# Driver3.net
KiCad netlist of a schematic drawn in Altium Designer
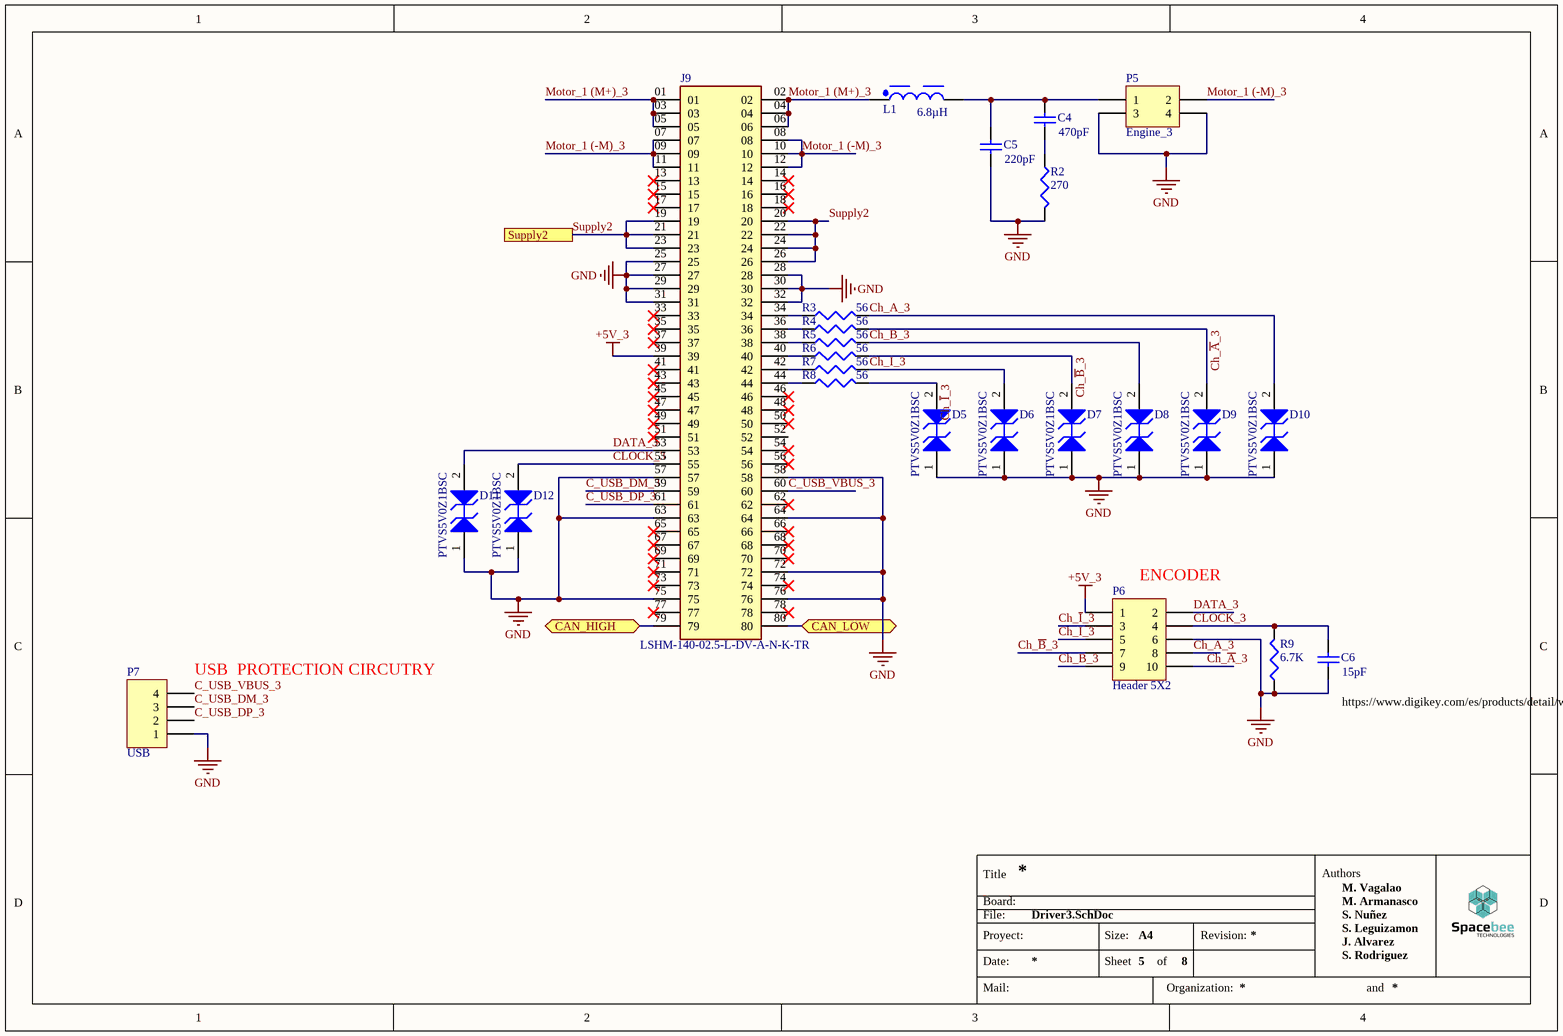
[diagram p0: Driver3.SchDoc]

(export (version "E")
  (design (tool "Eeschema 10.0.6"))
  (components
    (comp (ref "C4")
      (value "470pF")
      (footprint "1608[0603]")
      (description "Capacitor (Semiconductor SIM Model)")
      (fields (field (name "Comment") "Cap Semi") (field (name "PUBLISHER") "Altium Limited"))
      (libsource (lib "Miscellaneous Devices") (part "Cap Semi"))
    )
    (comp (ref "C5")
      (value "220pF")
      (footprint "1608[0603]")
      (description "Capacitor (Semiconductor SIM Model)")
      (fields (field (name "Comment") "Cap Semi") (field (name "PUBLISHER") "Altium Limited"))
      (libsource (lib "Miscellaneous Devices") (part "Cap Semi"))
    )
    (comp (ref "C6")
      (value "15pF")
      (footprint "1608[0603]")
      (description "Capacitor (Semiconductor SIM Model)")
      (fields (field (name "Comment") "Cap Semi") (field (name "PUBLISHER") "Altium Limited"))
      (libsource (lib "Miscellaneous Devices") (part "Cap Semi"))
    )
    (comp (ref "D5")
      (value "PTVS5V0Z1BSC")
      (footprint "SOD993B")
      (fields (field (name "MANUFACTURER") "On Semiconductor") (field (name "PARTNUMBER") "1SMB16CAT3"))
      (libsource (lib "DriverLib") (part "PTVS5V0Z1BSC"))
    )
    (comp (ref "D6")
      (value "PTVS5V0Z1BSC")
      (footprint "SOD993B")
      (fields (field (name "MANUFACTURER") "On Semiconductor") (field (name "PARTNUMBER") "1SMB16CAT3"))
      (libsource (lib "DriverLib") (part "PTVS5V0Z1BSC"))
    )
    (comp (ref "D7")
      (value "PTVS5V0Z1BSC")
      (footprint "SOD993B")
      (fields (field (name "MANUFACTURER") "On Semiconductor") (field (name "PARTNUMBER") "1SMB16CAT3"))
      (libsource (lib "DriverLib") (part "PTVS5V0Z1BSC"))
    )
    (comp (ref "D8")
      (value "PTVS5V0Z1BSC")
      (footprint "SOD993B")
      (fields (field (name "MANUFACTURER") "On Semiconductor") (field (name "PARTNUMBER") "1SMB16CAT3"))
      (libsource (lib "DriverLib") (part "PTVS5V0Z1BSC"))
    )
    (comp (ref "D9")
      (value "PTVS5V0Z1BSC")
      (footprint "SOD993B")
      (fields (field (name "MANUFACTURER") "On Semiconductor") (field (name "PARTNUMBER") "1SMB16CAT3"))
      (libsource (lib "DriverLib") (part "PTVS5V0Z1BSC"))
    )
    (comp (ref "D10")
      (value "PTVS5V0Z1BSC")
      (footprint "SOD993B")
      (fields (field (name "MANUFACTURER") "On Semiconductor") (field (name "PARTNUMBER") "1SMB16CAT3"))
      (libsource (lib "DriverLib") (part "PTVS5V0Z1BSC"))
    )
    (comp (ref "D11")
      (value "PTVS5V0Z1BSC")
      (footprint "SOD993B")
      (fields (field (name "MANUFACTURER") "On Semiconductor") (field (name "PARTNUMBER") "1SMB16CAT3"))
      (libsource (lib "DriverLib") (part "PTVS5V0Z1BSC"))
    )
    (comp (ref "D12")
      (value "PTVS5V0Z1BSC")
      (footprint "SOD993B")
      (fields (field (name "MANUFACTURER") "On Semiconductor") (field (name "PARTNUMBER") "1SMB16CAT3"))
      (libsource (lib "DriverLib") (part "PTVS5V0Z1BSC"))
    )
    (comp (ref "J9")
      (value "LSHM-140-02.5-L-DV-A-N-K-TR")
      (footprint "SAMTEC_LSHM-140-02.5-L-DV-A-N-K-TR")
      (description "LSHM - Samtec 0.50mm Razor Beam High-Speed Hermaphroditic Terminal / Socket Strip.")
      (libsource (lib "DriverLib") (part "LSHM-140-02.5-L-DV-A-N-K-TR"))
    )
    (comp (ref "L1")
      (value "6.8µH")
      (footprint "WE-XHMA_6060")
      (description "WE-XHMA SMD Power Inductor, size 1090, 6.8µH, 10.5A, 7.16mΩ")
      (fields
        (field (name "MANUFACTURER PART NUMBER") "78439369068")
        (field (name "MANUFACTURER") "Wurth Elektronik")
      )
      (libsource (lib "DriverLib") (part "78439369068"))
    )
    (comp (ref "P5")
      (value "Engine_3")
      (footprint "MOLEX_1724480004")
      (description "Header, 2-Pin, Dual row")
      (fields (field (name "PUBLISHER") "Altium Limited"))
      (libsource (lib "SpaceBee") (part "Header 2X2"))
    )
    (comp (ref "P6")
      (value "Header 5X2")
      (footprint "CONN_HIF3FC-14PA-2.54DS(71)_HIR")
      (description "Header, 5-Pin, Dual row")
      (fields (field (name "PUBLISHER") "Altium Limited"))
      (libsource (lib "DriverLib") (part "Header 5X2"))
    )
    (comp (ref "P7")
      (value "USB")
      (footprint "HDR1X4")
      (description "Header, 4-Pin")
      (fields (field (name "PUBLISHER") "Altium Limited"))
      (libsource (lib "Miscellaneous Connectors") (part "Header 4"))
    )
    (comp (ref "R2")
      (value "270")
      (footprint "J1-0603")
      (description "Resistor")
      (fields (field (name "Comment") "Res3") (field (name "PUBLISHER") "Altium Limited"))
      (libsource (lib "Miscellaneous Devices") (part "Res3"))
    )
    (comp (ref "R3")
      (value "56")
      (footprint "J1-0603")
      (description "Resistor")
      (fields (field (name "Comment") "Res3") (field (name "PUBLISHER") "Altium Limited"))
      (libsource (lib "Miscellaneous Devices") (part "Res3"))
    )
    (comp (ref "R4")
      (value "56")
      (footprint "J1-0603")
      (description "Resistor")
      (fields (field (name "Comment") "Res3") (field (name "PUBLISHER") "Altium Limited"))
      (libsource (lib "Miscellaneous Devices") (part "Res3"))
    )
    (comp (ref "R5")
      (value "56")
      (footprint "J1-0603")
      (description "Resistor")
      (fields (field (name "Comment") "Res3") (field (name "PUBLISHER") "Altium Limited"))
      (libsource (lib "Miscellaneous Devices") (part "Res3"))
    )
    (comp (ref "R6")
      (value "56")
      (footprint "J1-0603")
      (description "Resistor")
      (fields (field (name "Comment") "Res3") (field (name "PUBLISHER") "Altium Limited"))
      (libsource (lib "Miscellaneous Devices") (part "Res3"))
    )
    (comp (ref "R7")
      (value "56")
      (footprint "J1-0603")
      (description "Resistor")
      (fields (field (name "Comment") "Res3") (field (name "PUBLISHER") "Altium Limited"))
      (libsource (lib "Miscellaneous Devices") (part "Res3"))
    )
    (comp (ref "R8")
      (value "56")
      (footprint "J1-0603")
      (description "Resistor")
      (fields (field (name "Comment") "Res3") (field (name "PUBLISHER") "Altium Limited"))
      (libsource (lib "Miscellaneous Devices") (part "Res3"))
    )
    (comp (ref "R9")
      (value "6.7K")
      (footprint "J1-0603")
      (description "Resistor")
      (fields (field (name "Comment") "Res3") (field (name "PUBLISHER") "Altium Limited"))
      (libsource (lib "Miscellaneous Devices") (part "Res3"))
    )
  )
  (nets
    (net (code "1") (name "+5V_3") (class "Default")
      (node (ref "J9") (pin "39") (pinfunction "39_39") (pintype "passive"))
      (node (ref "P6") (pin "1") (pinfunction "1_1") (pintype "passive"))
    )
    (net (code "2") (name "/CAN_HIGH") (class "Default")
      (node (ref "J9") (pin "79") (pinfunction "79_79") (pintype "passive"))
    )
    (net (code "3") (name "/CAN_LOW") (class "Default")
      (node (ref "J9") (pin "80") (pinfunction "80_80") (pintype "passive"))
    )
    (net (code "4") (name "/CLOCK_3") (class "Default")
      (node (ref "C6") (pin "1") (pinfunction "1_1") (pintype "passive"))
      (node (ref "D12") (pin "2") (pinfunction "A2_2") (pintype "passive"))
      (node (ref "J9") (pin "55") (pinfunction "55_55") (pintype "passive"))
      (node (ref "P6") (pin "4") (pinfunction "4_4") (pintype "passive"))
      (node (ref "R9") (pin "2") (pinfunction "2_2") (pintype "passive"))
    )
    (net (code "5") (name "/C_USB_DM_3") (class "Default")
      (node (ref "J9") (pin "59") (pinfunction "59_59") (pintype "passive"))
      (node (ref "P7") (pin "3") (pinfunction "3_3") (pintype "passive"))
    )
    (net (code "6") (name "/C_USB_DP_3") (class "Default")
      (node (ref "J9") (pin "61") (pinfunction "61_61") (pintype "passive"))
      (node (ref "P7") (pin "2") (pinfunction "2_2") (pintype "passive"))
    )
    (net (code "7") (name "/C_USB_VBUS_3") (class "Default")
      (node (ref "J9") (pin "60") (pinfunction "60_60") (pintype "passive"))
      (node (ref "P7") (pin "4") (pinfunction "4_4") (pintype "passive"))
    )
    (net (code "8") (name "/Ch_A_3") (class "Default")
      (node (ref "D10") (pin "2") (pinfunction "A2_2") (pintype "passive"))
      (node (ref "P6") (pin "8") (pinfunction "8_8") (pintype "passive"))
      (node (ref "R3") (pin "2") (pinfunction "2_2") (pintype "passive"))
    )
    (net (code "9") (name "/Ch_B_3") (class "Default")
      (node (ref "D8") (pin "2") (pinfunction "A2_2") (pintype "passive"))
      (node (ref "P6") (pin "9") (pinfunction "9_9") (pintype "passive"))
      (node (ref "R5") (pin "2") (pinfunction "2_2") (pintype "passive"))
    )
    (net (code "10") (name "/Ch_I_3") (class "Default")
      (node (ref "D6") (pin "2") (pinfunction "A2_2") (pintype "passive"))
      (node (ref "P6") (pin "5") (pinfunction "5_5") (pintype "passive"))
      (node (ref "R7") (pin "2") (pinfunction "2_2") (pintype "passive"))
    )
    (net (code "11") (name "/Ch_~{A}_3") (class "Default")
      (node (ref "D9") (pin "2") (pinfunction "A2_2") (pintype "passive"))
      (node (ref "P6") (pin "10") (pinfunction "10_10") (pintype "passive"))
      (node (ref "R4") (pin "2") (pinfunction "2_2") (pintype "passive"))
    )
    (net (code "12") (name "/Ch_~{B}_3") (class "Default")
      (node (ref "D7") (pin "2") (pinfunction "A2_2") (pintype "passive"))
      (node (ref "P6") (pin "7") (pinfunction "7_7") (pintype "passive"))
      (node (ref "R6") (pin "2") (pinfunction "2_2") (pintype "passive"))
    )
    (net (code "13") (name "/Ch_~{I}_3") (class "Default")
      (node (ref "D5") (pin "2") (pinfunction "A2_2") (pintype "passive"))
      (node (ref "P6") (pin "3") (pinfunction "3_3") (pintype "passive"))
      (node (ref "R8") (pin "2") (pinfunction "2_2") (pintype "passive"))
    )
    (net (code "14") (name "/DATA_3") (class "Default")
      (node (ref "D11") (pin "2") (pinfunction "A2_2") (pintype "passive"))
      (node (ref "J9") (pin "53") (pinfunction "53_53") (pintype "passive"))
      (node (ref "P6") (pin "2") (pinfunction "2_2") (pintype "passive"))
    )
    (net (code "15") (name "/Motor_1 (-M)_3") (class "Default")
      (node (ref "J9") (pin "07") (pinfunction "07_07") (pintype "passive"))
      (node (ref "J9") (pin "08") (pinfunction "08_08") (pintype "passive"))
      (node (ref "J9") (pin "09") (pinfunction "09_09") (pintype "passive"))
      (node (ref "J9") (pin "10") (pinfunction "10_10") (pintype "passive"))
      (node (ref "J9") (pin "11") (pinfunction "11_11") (pintype "passive"))
      (node (ref "J9") (pin "12") (pinfunction "12_12") (pintype "passive"))
      (node (ref "P5") (pin "2") (pinfunction "2_2") (pintype "passive"))
    )
    (net (code "16") (name "/Motor_1 (M+)_3") (class "Default")
      (node (ref "J9") (pin "01") (pinfunction "01_01") (pintype "passive"))
      (node (ref "J9") (pin "02") (pinfunction "02_02") (pintype "passive"))
      (node (ref "J9") (pin "03") (pinfunction "03_03") (pintype "passive"))
      (node (ref "J9") (pin "04") (pinfunction "04_04") (pintype "passive"))
      (node (ref "J9") (pin "05") (pinfunction "05_05") (pintype "passive"))
      (node (ref "J9") (pin "06") (pinfunction "06_06") (pintype "passive"))
      (node (ref "L1") (pin "1") (pinfunction "1_1") (pintype "passive"))
    )
    (net (code "17") (name "/Supply2") (class "Default")
      (node (ref "J9") (pin "19") (pinfunction "19_19") (pintype "passive"))
      (node (ref "J9") (pin "20") (pinfunction "20_20") (pintype "passive"))
      (node (ref "J9") (pin "21") (pinfunction "21_21") (pintype "passive"))
      (node (ref "J9") (pin "22") (pinfunction "22_22") (pintype "passive"))
      (node (ref "J9") (pin "23") (pinfunction "23_23") (pintype "passive"))
      (node (ref "J9") (pin "24") (pinfunction "24_24") (pintype "passive"))
      (node (ref "J9") (pin "26") (pinfunction "26_26") (pintype "passive"))
    )
    (net (code "18") (name "GND") (class "Default")
      (node (ref "C5") (pin "2") (pinfunction "2_2") (pintype "passive"))
      (node (ref "C6") (pin "2") (pinfunction "2_2") (pintype "passive"))
      (node (ref "D10") (pin "1") (pinfunction "A1_1") (pintype "passive"))
      (node (ref "D11") (pin "1") (pinfunction "A1_1") (pintype "passive"))
      (node (ref "D12") (pin "1") (pinfunction "A1_1") (pintype "passive"))
      (node (ref "D5") (pin "1") (pinfunction "A1_1") (pintype "passive"))
      (node (ref "D6") (pin "1") (pinfunction "A1_1") (pintype "passive"))
      (node (ref "D7") (pin "1") (pinfunction "A1_1") (pintype "passive"))
      (node (ref "D8") (pin "1") (pinfunction "A1_1") (pintype "passive"))
      (node (ref "D9") (pin "1") (pinfunction "A1_1") (pintype "passive"))
      (node (ref "J9") (pin "25") (pinfunction "25_25") (pintype "passive"))
      (node (ref "J9") (pin "27") (pinfunction "27_27") (pintype "passive"))
      (node (ref "J9") (pin "28") (pinfunction "28_28") (pintype "passive"))
      (node (ref "J9") (pin "29") (pinfunction "29_29") (pintype "passive"))
      (node (ref "J9") (pin "30") (pinfunction "30_30") (pintype "passive"))
      (node (ref "J9") (pin "31") (pinfunction "31_31") (pintype "passive"))
      (node (ref "J9") (pin "32") (pinfunction "32_32") (pintype "passive"))
      (node (ref "J9") (pin "57") (pinfunction "57_57") (pintype "passive"))
      (node (ref "J9") (pin "58") (pinfunction "58_58") (pintype "passive"))
      (node (ref "J9") (pin "63") (pinfunction "63_63") (pintype "passive"))
      (node (ref "J9") (pin "64") (pinfunction "64_64") (pintype "passive"))
      (node (ref "J9") (pin "72") (pinfunction "72_72") (pintype "passive"))
      (node (ref "J9") (pin "75") (pinfunction "75_75") (pintype "passive"))
      (node (ref "J9") (pin "76") (pinfunction "76_76") (pintype "passive"))
      (node (ref "P5") (pin "3") (pinfunction "3_3") (pintype "passive"))
      (node (ref "P5") (pin "4") (pinfunction "4_4") (pintype "passive"))
      (node (ref "P6") (pin "6") (pinfunction "6_6") (pintype "passive"))
      (node (ref "P7") (pin "1") (pinfunction "1_1") (pintype "passive"))
      (node (ref "R2") (pin "2") (pinfunction "2_2") (pintype "passive"))
      (node (ref "R9") (pin "1") (pinfunction "1_1") (pintype "passive"))
    )
    (net (code "19") (name "Net-(C4-Pad1)") (class "Default")
      (node (ref "C4") (pin "1") (pinfunction "1_1") (pintype "passive"))
      (node (ref "C5") (pin "1") (pinfunction "1_1") (pintype "passive"))
      (node (ref "L1") (pin "2") (pinfunction "2_2") (pintype "passive"))
      (node (ref "P5") (pin "1") (pinfunction "1_1") (pintype "passive"))
    )
    (net (code "20") (name "Net-(C4-Pad2)") (class "Default")
      (node (ref "C4") (pin "2") (pinfunction "2_2") (pintype "passive"))
      (node (ref "R2") (pin "1") (pinfunction "1_1") (pintype "passive"))
    )
    (net (code "21") (name "Net-(J9-Pad34)") (class "Default")
      (node (ref "J9") (pin "34") (pinfunction "34_34") (pintype "passive"))
      (node (ref "R3") (pin "1") (pinfunction "1_1") (pintype "passive"))
    )
    (net (code "22") (name "Net-(J9-Pad36)") (class "Default")
      (node (ref "J9") (pin "36") (pinfunction "36_36") (pintype "passive"))
      (node (ref "R4") (pin "1") (pinfunction "1_1") (pintype "passive"))
    )
    (net (code "23") (name "Net-(J9-Pad38)") (class "Default")
      (node (ref "J9") (pin "38") (pinfunction "38_38") (pintype "passive"))
      (node (ref "R5") (pin "1") (pinfunction "1_1") (pintype "passive"))
    )
    (net (code "24") (name "Net-(J9-Pad40)") (class "Default")
      (node (ref "J9") (pin "40") (pinfunction "40_40") (pintype "passive"))
      (node (ref "R6") (pin "1") (pinfunction "1_1") (pintype "passive"))
    )
    (net (code "25") (name "Net-(J9-Pad42)") (class "Default")
      (node (ref "J9") (pin "42") (pinfunction "42_42") (pintype "passive"))
      (node (ref "R7") (pin "1") (pinfunction "1_1") (pintype "passive"))
    )
    (net (code "26") (name "Net-(J9-Pad44)") (class "Default")
      (node (ref "J9") (pin "44") (pinfunction "44_44") (pintype "passive"))
      (node (ref "R8") (pin "1") (pinfunction "1_1") (pintype "passive"))
    )
    (net (code "27") (name "unconnected-(J9-Pad13)") (class "Default")
      (node (ref "J9") (pin "13") (pinfunction "13_13") (pintype "passive+no_connect"))
    )
    (net (code "28") (name "unconnected-(J9-Pad14)") (class "Default")
      (node (ref "J9") (pin "14") (pinfunction "14_14") (pintype "passive+no_connect"))
    )
    (net (code "29") (name "unconnected-(J9-Pad15)") (class "Default")
      (node (ref "J9") (pin "15") (pinfunction "15_15") (pintype "passive+no_connect"))
    )
    (net (code "30") (name "unconnected-(J9-Pad16)") (class "Default")
      (node (ref "J9") (pin "16") (pinfunction "16_16") (pintype "passive+no_connect"))
    )
    (net (code "31") (name "unconnected-(J9-Pad17)") (class "Default")
      (node (ref "J9") (pin "17") (pinfunction "17_17") (pintype "passive+no_connect"))
    )
    (net (code "32") (name "unconnected-(J9-Pad18)") (class "Default")
      (node (ref "J9") (pin "18") (pinfunction "18_18") (pintype "passive+no_connect"))
    )
    (net (code "33") (name "unconnected-(J9-Pad33)") (class "Default")
      (node (ref "J9") (pin "33") (pinfunction "33_33") (pintype "passive+no_connect"))
    )
    (net (code "34") (name "unconnected-(J9-Pad35)") (class "Default")
      (node (ref "J9") (pin "35") (pinfunction "35_35") (pintype "passive+no_connect"))
    )
    (net (code "35") (name "unconnected-(J9-Pad37)") (class "Default")
      (node (ref "J9") (pin "37") (pinfunction "37_37") (pintype "passive+no_connect"))
    )
    (net (code "36") (name "unconnected-(J9-Pad41)") (class "Default")
      (node (ref "J9") (pin "41") (pinfunction "41_41") (pintype "passive+no_connect"))
    )
    (net (code "37") (name "unconnected-(J9-Pad43)") (class "Default")
      (node (ref "J9") (pin "43") (pinfunction "43_43") (pintype "passive+no_connect"))
    )
    (net (code "38") (name "unconnected-(J9-Pad45)") (class "Default")
      (node (ref "J9") (pin "45") (pinfunction "45_45") (pintype "passive+no_connect"))
    )
    (net (code "39") (name "unconnected-(J9-Pad46)") (class "Default")
      (node (ref "J9") (pin "46") (pinfunction "46_46") (pintype "passive+no_connect"))
    )
    (net (code "40") (name "unconnected-(J9-Pad47)") (class "Default")
      (node (ref "J9") (pin "47") (pinfunction "47_47") (pintype "passive+no_connect"))
    )
    (net (code "41") (name "unconnected-(J9-Pad48)") (class "Default")
      (node (ref "J9") (pin "48") (pinfunction "48_48") (pintype "passive+no_connect"))
    )
    (net (code "42") (name "unconnected-(J9-Pad49)") (class "Default")
      (node (ref "J9") (pin "49") (pinfunction "49_49") (pintype "passive+no_connect"))
    )
    (net (code "43") (name "unconnected-(J9-Pad50)") (class "Default")
      (node (ref "J9") (pin "50") (pinfunction "50_50") (pintype "passive+no_connect"))
    )
    (net (code "44") (name "unconnected-(J9-Pad51)") (class "Default")
      (node (ref "J9") (pin "51") (pinfunction "51_51") (pintype "passive+no_connect"))
    )
    (net (code "45") (name "unconnected-(J9-Pad52)") (class "Default")
      (node (ref "J9") (pin "52") (pinfunction "52_52") (pintype "passive"))
    )
    (net (code "46") (name "unconnected-(J9-Pad54)") (class "Default")
      (node (ref "J9") (pin "54") (pinfunction "54_54") (pintype "passive+no_connect"))
    )
    (net (code "47") (name "unconnected-(J9-Pad56)") (class "Default")
      (node (ref "J9") (pin "56") (pinfunction "56_56") (pintype "passive+no_connect"))
    )
    (net (code "48") (name "unconnected-(J9-Pad62)") (class "Default")
      (node (ref "J9") (pin "62") (pinfunction "62_62") (pintype "passive+no_connect"))
    )
    (net (code "49") (name "unconnected-(J9-Pad65)") (class "Default")
      (node (ref "J9") (pin "65") (pinfunction "65_65") (pintype "passive+no_connect"))
    )
    (net (code "50") (name "unconnected-(J9-Pad66)") (class "Default")
      (node (ref "J9") (pin "66") (pinfunction "66_66") (pintype "passive+no_connect"))
    )
    (net (code "51") (name "unconnected-(J9-Pad67)") (class "Default")
      (node (ref "J9") (pin "67") (pinfunction "67_67") (pintype "passive+no_connect"))
    )
    (net (code "52") (name "unconnected-(J9-Pad68)") (class "Default")
      (node (ref "J9") (pin "68") (pinfunction "68_68") (pintype "passive+no_connect"))
    )
    (net (code "53") (name "unconnected-(J9-Pad69)") (class "Default")
      (node (ref "J9") (pin "69") (pinfunction "69_69") (pintype "passive+no_connect"))
    )
    (net (code "54") (name "unconnected-(J9-Pad70)") (class "Default")
      (node (ref "J9") (pin "70") (pinfunction "70_70") (pintype "passive+no_connect"))
    )
    (net (code "55") (name "unconnected-(J9-Pad71)") (class "Default")
      (node (ref "J9") (pin "71") (pinfunction "71_71") (pintype "passive+no_connect"))
    )
    (net (code "56") (name "unconnected-(J9-Pad73)") (class "Default")
      (node (ref "J9") (pin "73") (pinfunction "73_73") (pintype "passive+no_connect"))
    )
    (net (code "57") (name "unconnected-(J9-Pad74)") (class "Default")
      (node (ref "J9") (pin "74") (pinfunction "74_74") (pintype "passive+no_connect"))
    )
    (net (code "58") (name "unconnected-(J9-Pad77)") (class "Default")
      (node (ref "J9") (pin "77") (pinfunction "77_77") (pintype "passive+no_connect"))
    )
    (net (code "59") (name "unconnected-(J9-Pad78)") (class "Default")
      (node (ref "J9") (pin "78") (pinfunction "78_78") (pintype "passive+no_connect"))
    )
  )
)
